# fbri_flight_straight.net
KiCad netlist of a schematic drawn in EAGLE
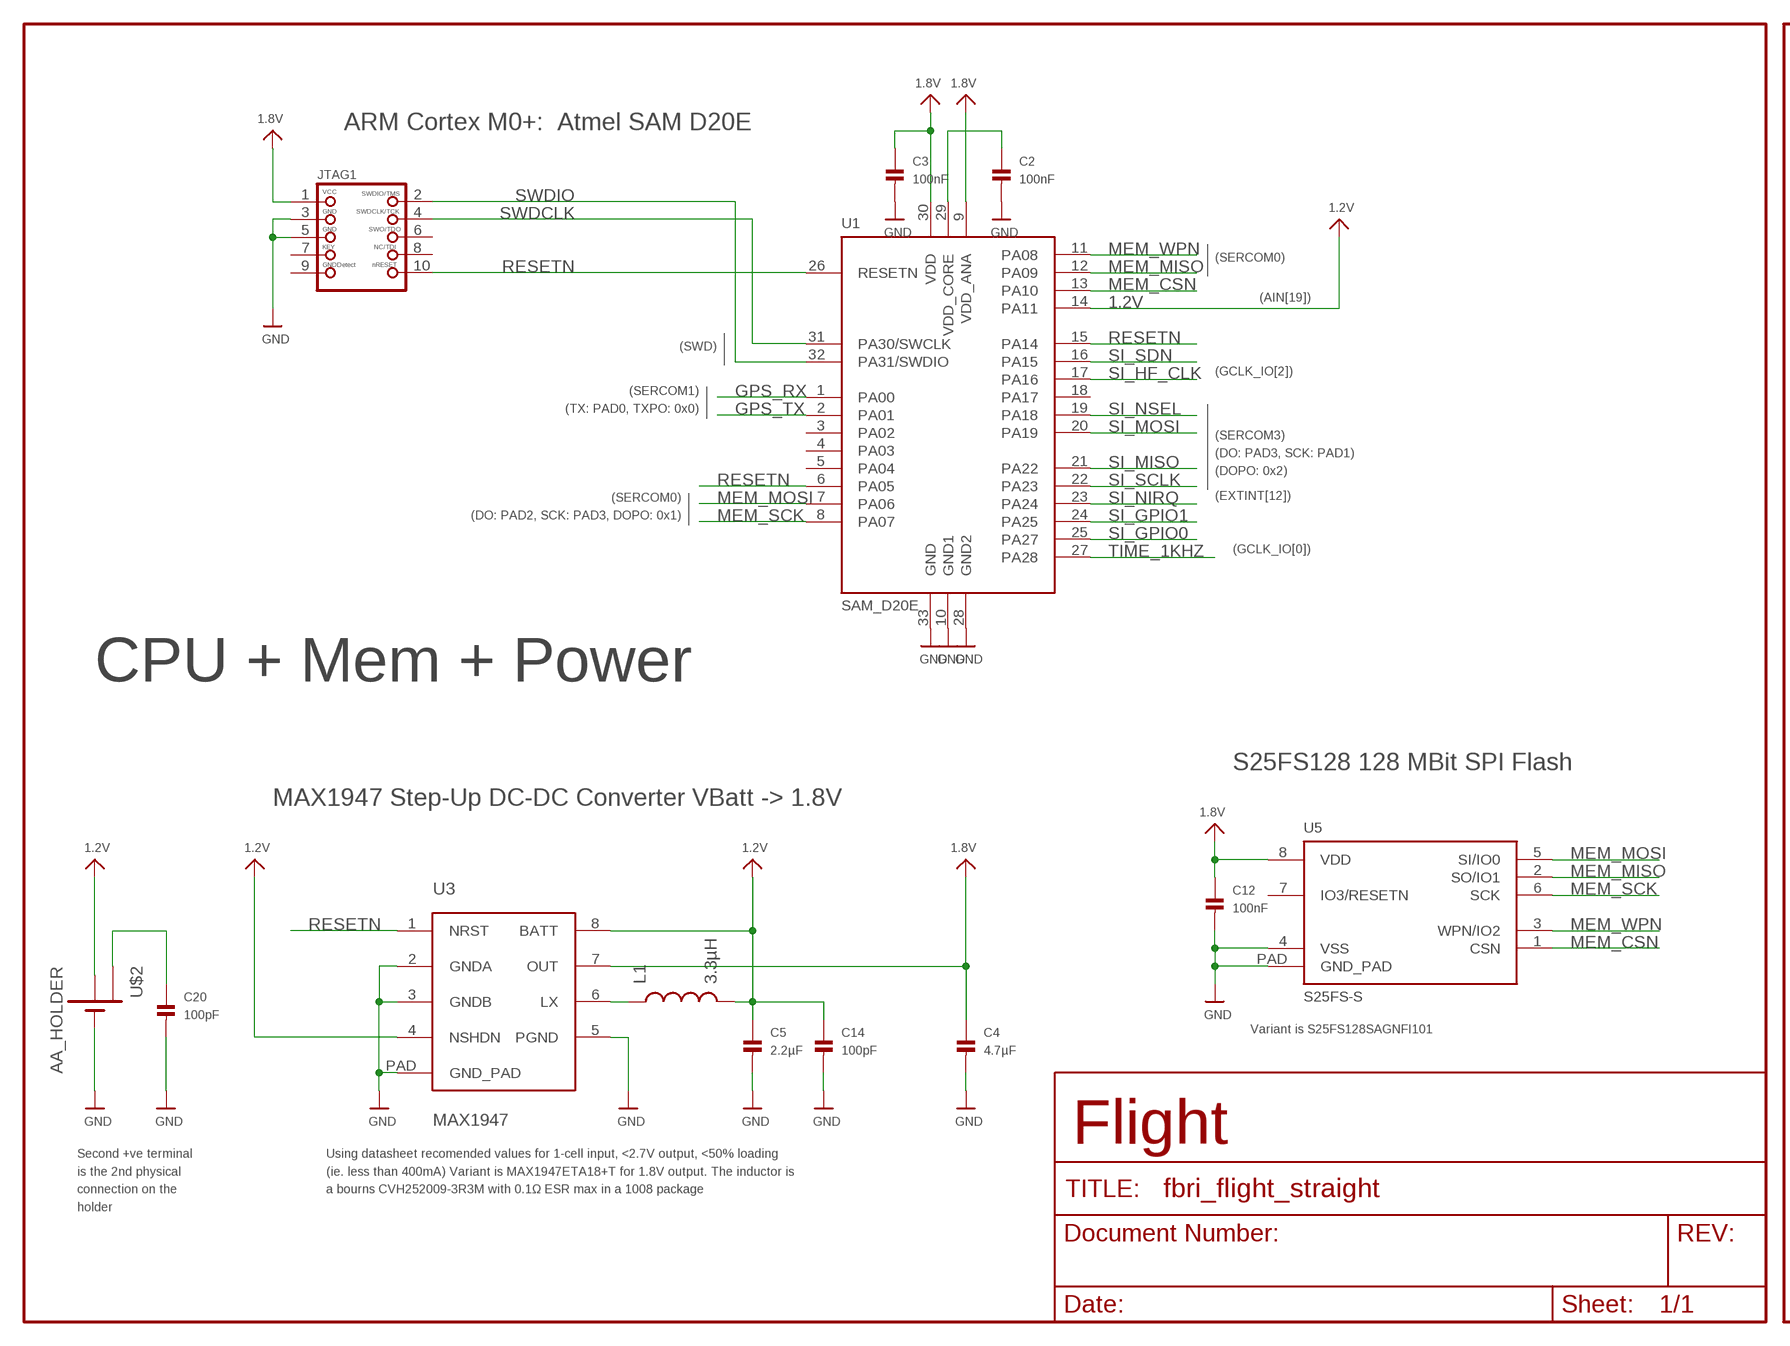
[diagram p0: schematic, sheet 1, part 1 of 2]
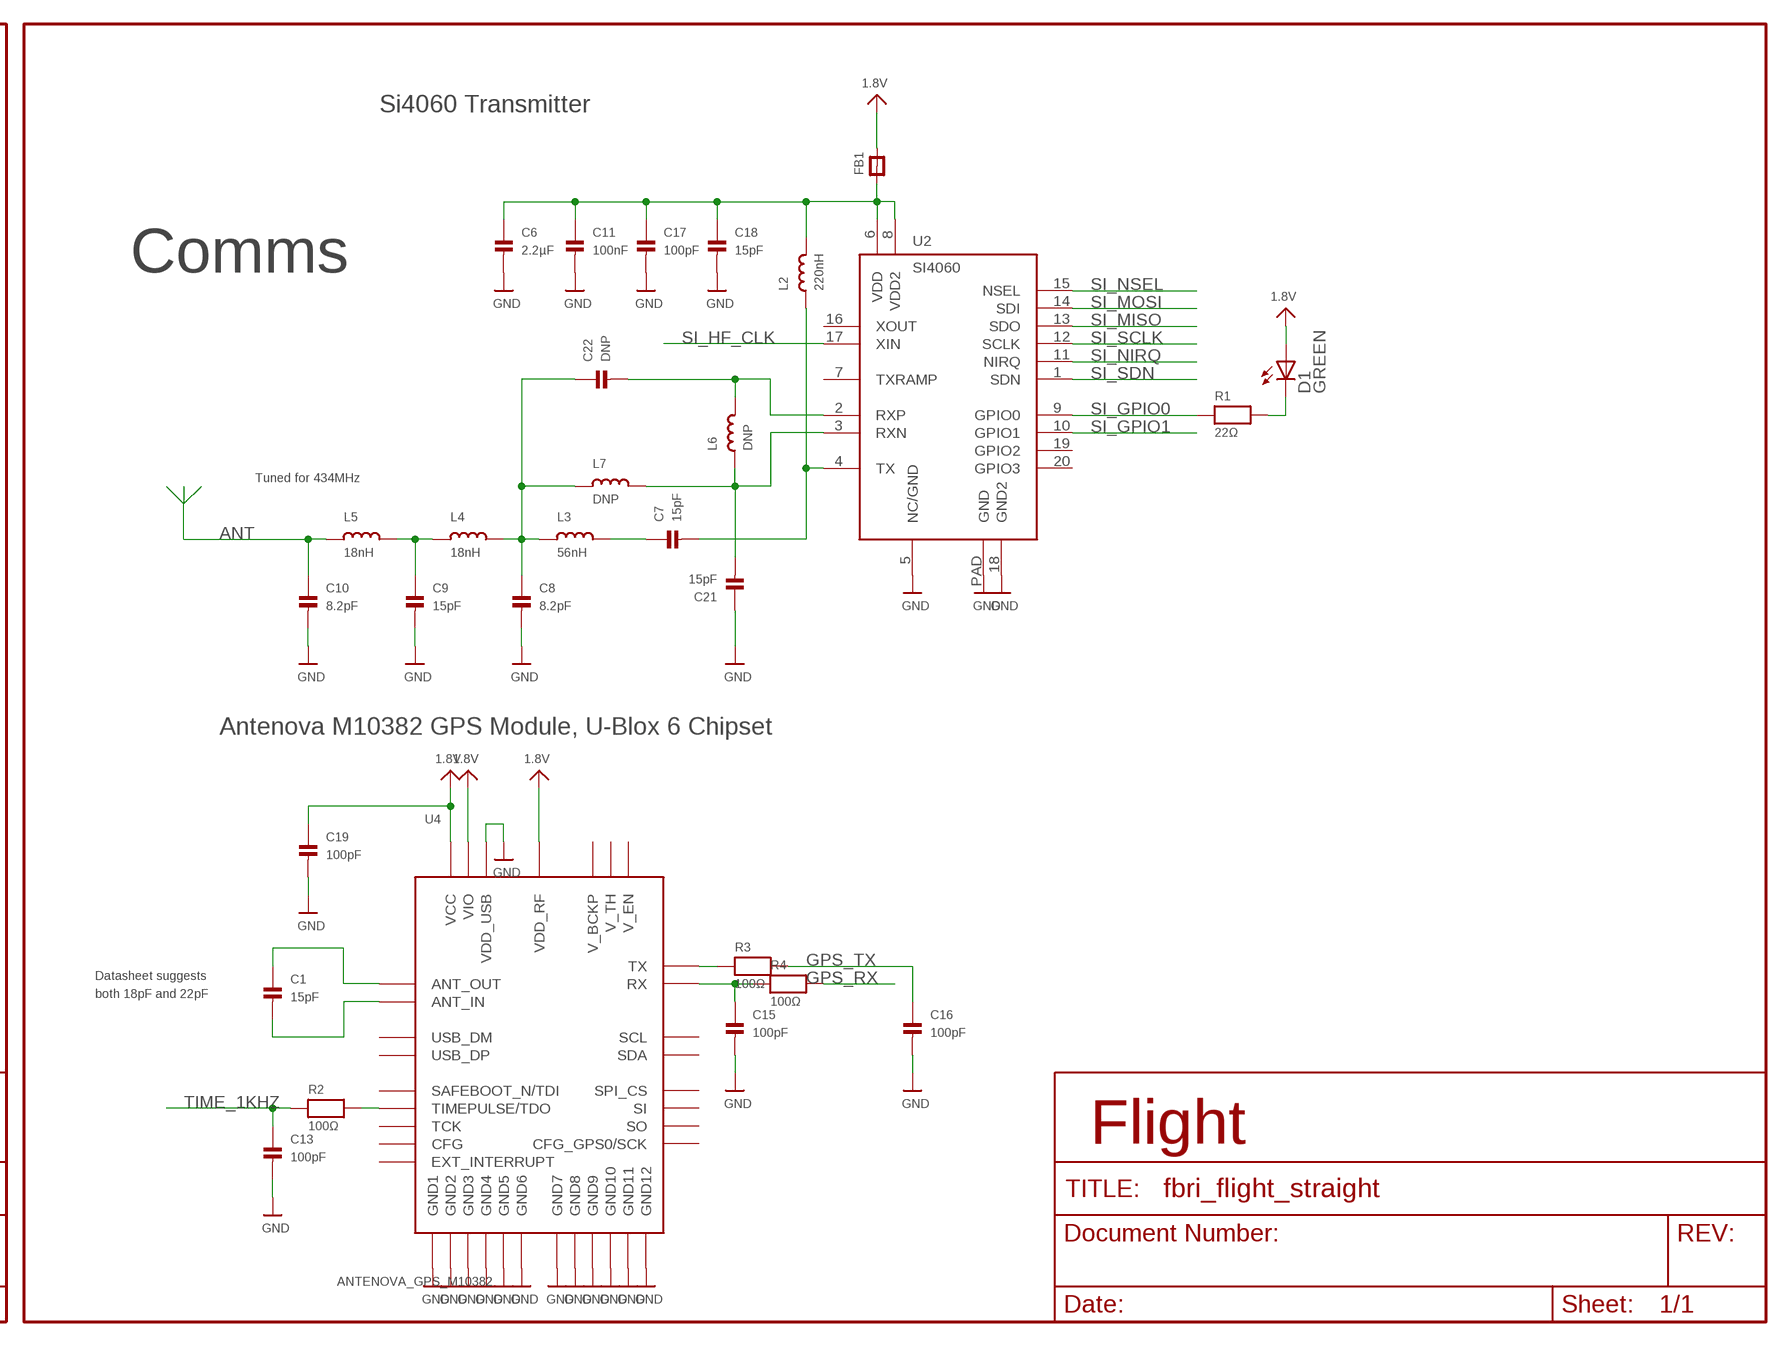
[diagram p1: schematic, sheet 1, part 2 of 2]

(export (version "E")
  (design (tool "Eeschema 10.0.6"))
  (components
    (comp (ref "C1")
      (value "15pF")
      (footprint "eagle-import:_0402")
      (libsource (lib "eagle-import") (part "CAP_CERAMIC_0402"))
    )
    (comp (ref "C2")
      (value "100nF")
      (footprint "eagle-import:_0402")
      (libsource (lib "eagle-import") (part "CAP_CERAMIC_0402"))
    )
    (comp (ref "C3")
      (value "100nF")
      (footprint "eagle-import:_0402")
      (libsource (lib "eagle-import") (part "CAP_CERAMIC_0402"))
    )
    (comp (ref "C4")
      (value "4.7µF")
      (footprint "eagle-import:_0402")
      (libsource (lib "eagle-import") (part "CAP_CERAMIC_0402"))
    )
    (comp (ref "C5")
      (value "2.2µF")
      (footprint "eagle-import:_0402")
      (libsource (lib "eagle-import") (part "CAP_CERAMIC_0402"))
    )
    (comp (ref "C6")
      (value "2.2µF")
      (footprint "eagle-import:_0402")
      (libsource (lib "eagle-import") (part "CAP_CERAMIC_0402"))
    )
    (comp (ref "C7")
      (value "15pF")
      (footprint "eagle-import:_0402")
      (libsource (lib "eagle-import") (part "CAP_CERAMIC_0402"))
    )
    (comp (ref "C8")
      (value "8.2pF")
      (footprint "eagle-import:_0402")
      (libsource (lib "eagle-import") (part "CAP_CERAMIC_0402"))
    )
    (comp (ref "C9")
      (value "15pF")
      (footprint "eagle-import:_0402")
      (libsource (lib "eagle-import") (part "CAP_CERAMIC_0402"))
    )
    (comp (ref "C10")
      (value "8.2pF")
      (footprint "eagle-import:_0402")
      (libsource (lib "eagle-import") (part "CAP_CERAMIC_0402"))
    )
    (comp (ref "C11")
      (value "100nF")
      (footprint "eagle-import:_0402")
      (libsource (lib "eagle-import") (part "CAP_CERAMIC_0402"))
    )
    (comp (ref "C12")
      (value "100nF")
      (footprint "eagle-import:_0402")
      (libsource (lib "eagle-import") (part "CAP_CERAMIC_0402"))
    )
    (comp (ref "C13")
      (value "100pF")
      (footprint "eagle-import:_0402")
      (libsource (lib "eagle-import") (part "CAP_CERAMIC_0402"))
    )
    (comp (ref "C14")
      (value "100pF")
      (footprint "eagle-import:_0402")
      (libsource (lib "eagle-import") (part "CAP_CERAMIC_0402"))
    )
    (comp (ref "C15")
      (value "100pF")
      (footprint "eagle-import:_0402")
      (libsource (lib "eagle-import") (part "CAP_CERAMIC_0402"))
    )
    (comp (ref "C16")
      (value "100pF")
      (footprint "eagle-import:_0402")
      (libsource (lib "eagle-import") (part "CAP_CERAMIC_0402"))
    )
    (comp (ref "C17")
      (value "100pF")
      (footprint "eagle-import:_0402")
      (libsource (lib "eagle-import") (part "CAP_CERAMIC_0402"))
    )
    (comp (ref "C18")
      (value "15pF")
      (footprint "eagle-import:_0402")
      (libsource (lib "eagle-import") (part "CAP_CERAMIC_0402"))
    )
    (comp (ref "C19")
      (value "100pF")
      (footprint "eagle-import:_0402")
      (libsource (lib "eagle-import") (part "CAP_CERAMIC_0402"))
    )
    (comp (ref "C20")
      (value "100pF")
      (footprint "eagle-import:_0402")
      (libsource (lib "eagle-import") (part "CAP_CERAMIC_0402"))
    )
    (comp (ref "C21")
      (value "15pF")
      (footprint "eagle-import:_0402")
      (libsource (lib "eagle-import") (part "CAP_CERAMIC_0402"))
    )
    (comp (ref "C22")
      (value "DNP")
      (footprint "eagle-import:_0402")
      (libsource (lib "eagle-import") (part "CAP_CERAMIC_0402"))
    )
    (comp (ref "D1")
      (value "GREEN")
      (footprint "eagle-import:CHIPLED_0603")
      (libsource (lib "eagle-import") (part "LEDCHIPLED_0603"))
    )
    (comp (ref "FB1")
      (value "FERRITE_0402")
      (footprint "eagle-import:_0402")
      (libsource (lib "eagle-import") (part "FERRITE_0402"))
    )
    (comp (ref "JTAG1")
      (value "JTAG-CORTEXM3SMT")
      (footprint "eagle-import:2X05_1.27MM_SMT")
      (libsource (lib "eagle-import") (part "JTAG-CORTEXM3SMT"))
    )
    (comp (ref "L1")
      (value "3.3µH")
      (footprint "eagle-import:1007")
      (libsource (lib "eagle-import") (part "INDUCTOR1007"))
    )
    (comp (ref "L2")
      (value "220nH")
      (footprint "eagle-import:_0402")
      (libsource (lib "eagle-import") (part "INDUCTOR_0402"))
    )
    (comp (ref "L3")
      (value "56nH")
      (footprint "eagle-import:_0402")
      (libsource (lib "eagle-import") (part "INDUCTOR_0402"))
    )
    (comp (ref "L4")
      (value "18nH")
      (footprint "eagle-import:_0402")
      (libsource (lib "eagle-import") (part "INDUCTOR_0402"))
    )
    (comp (ref "L5")
      (value "18nH")
      (footprint "eagle-import:_0402")
      (libsource (lib "eagle-import") (part "INDUCTOR_0402"))
    )
    (comp (ref "L6")
      (value "DNP")
      (footprint "eagle-import:_0402")
      (libsource (lib "eagle-import") (part "INDUCTOR_0402"))
    )
    (comp (ref "L7")
      (value "DNP")
      (footprint "eagle-import:_0402")
      (libsource (lib "eagle-import") (part "INDUCTOR_0402"))
    )
    (comp (ref "R1")
      (value "22Ω")
      (footprint "eagle-import:_0402")
      (libsource (lib "eagle-import") (part "RESISTOR_0402"))
    )
    (comp (ref "R2")
      (value "100Ω")
      (footprint "eagle-import:_0402")
      (libsource (lib "eagle-import") (part "RESISTOR_0402"))
    )
    (comp (ref "R3")
      (value "100Ω")
      (footprint "eagle-import:_0402")
      (libsource (lib "eagle-import") (part "RESISTOR_0402"))
    )
    (comp (ref "R4")
      (value "100Ω")
      (footprint "eagle-import:_0402")
      (libsource (lib "eagle-import") (part "RESISTOR_0402"))
    )
    (comp (ref "U$2")
      (value "AA_HOLDER")
      (footprint "eagle-import:AA")
      (libsource (lib "eagle-import") (part "AA_HOLDER"))
    )
    (comp (ref "U1")
      (value "SAM_D20E")
      (footprint "eagle-import:QFN32_5MM")
      (libsource (lib "eagle-import") (part "SAM_D20E"))
    )
    (comp (ref "U2")
      (value "SI4060")
      (footprint "eagle-import:QFN20")
      (libsource (lib "eagle-import") (part "SI4060"))
    )
    (comp (ref "U3")
      (value "MAX1947")
      (footprint "eagle-import:TDFN8")
      (libsource (lib "eagle-import") (part "MAX1947"))
    )
    (comp (ref "U4")
      (value "ANTENOVA_GPS_M10382")
      (footprint "eagle-import:ANTENOVA_GPS_M10382")
      (libsource (lib "eagle-import") (part "ANTENOVA_GPS_M10382"))
    )
    (comp (ref "U5")
      (value "S25FS-S")
      (footprint "eagle-import:WSON8")
      (libsource (lib "eagle-import") (part "S25FS-S"))
    )
  )
  (nets
    (net (code "1") (name "/ANT") (class "Default")
      (node (ref "C10") (pin "1") (pinfunction "P$1_1") (pintype "passive"))
      (node (ref "L5") (pin "1") (pinfunction "1_1") (pintype "passive"))
    )
    (net (code "2") (name "/GPS_RX") (class "Default")
      (node (ref "R4") (pin "2") (pinfunction "2_2") (pintype "passive"))
      (node (ref "U1") (pin "1") (pinfunction "PA00_1") (pintype "bidirectional"))
    )
    (net (code "3") (name "/GPS_TX") (class "Default")
      (node (ref "C16") (pin "1") (pinfunction "P$1_1") (pintype "passive"))
      (node (ref "R3") (pin "2") (pinfunction "2_2") (pintype "passive"))
      (node (ref "U1") (pin "2") (pinfunction "PA01_2") (pintype "bidirectional"))
    )
    (net (code "4") (name "/MEM_CSN") (class "Default")
      (node (ref "U1") (pin "13") (pinfunction "PA10_13") (pintype "bidirectional"))
      (node (ref "U5") (pin "1") (pinfunction "CSN_1") (pintype "input"))
    )
    (net (code "5") (name "/MEM_MISO") (class "Default")
      (node (ref "U1") (pin "12") (pinfunction "PA09_12") (pintype "bidirectional"))
      (node (ref "U5") (pin "2") (pinfunction "SO/IO1_2") (pintype "output"))
    )
    (net (code "6") (name "/MEM_MOSI") (class "Default")
      (node (ref "U1") (pin "7") (pinfunction "PA06_7") (pintype "bidirectional"))
      (node (ref "U5") (pin "5") (pinfunction "SI/IO0_5") (pintype "bidirectional"))
    )
    (net (code "7") (name "/MEM_SCK") (class "Default")
      (node (ref "U1") (pin "8") (pinfunction "PA07_8") (pintype "bidirectional"))
      (node (ref "U5") (pin "6") (pinfunction "SCK_6") (pintype "input"))
    )
    (net (code "8") (name "/MEM_WPN") (class "Default")
      (node (ref "U1") (pin "11") (pinfunction "PA08_11") (pintype "bidirectional"))
      (node (ref "U5") (pin "3") (pinfunction "WPN/IO2_3") (pintype "output"))
    )
    (net (code "9") (name "/RESETN") (class "Default")
      (node (ref "JTAG1") (pin "10") (pinfunction "10_10") (pintype "passive"))
      (node (ref "U1") (pin "15") (pinfunction "PA14_15") (pintype "bidirectional"))
      (node (ref "U1") (pin "26") (pinfunction "RESETN_26") (pintype "input"))
      (node (ref "U1") (pin "6") (pinfunction "PA05_6") (pintype "bidirectional"))
      (node (ref "U3") (pin "1") (pinfunction "NRST_1") (pintype "bidirectional"))
    )
    (net (code "10") (name "/SI_GPIO0") (class "Default")
      (node (ref "R1") (pin "1") (pinfunction "1_1") (pintype "passive"))
      (node (ref "U1") (pin "25") (pinfunction "PA27_25") (pintype "bidirectional"))
      (node (ref "U2") (pin "9") (pinfunction "GPIO0_9") (pintype "bidirectional"))
    )
    (net (code "11") (name "/SI_GPIO1") (class "Default")
      (node (ref "U1") (pin "24") (pinfunction "PA25_24") (pintype "bidirectional"))
      (node (ref "U2") (pin "10") (pinfunction "GPIO1_10") (pintype "bidirectional"))
    )
    (net (code "12") (name "/SI_HF_CLK") (class "Default")
      (node (ref "U1") (pin "17") (pinfunction "PA16_17") (pintype "bidirectional"))
      (node (ref "U2") (pin "17") (pinfunction "XIN_17") (pintype "input"))
    )
    (net (code "13") (name "/SI_MISO") (class "Default")
      (node (ref "U1") (pin "21") (pinfunction "PA22_21") (pintype "bidirectional"))
      (node (ref "U2") (pin "13") (pinfunction "SDO_13") (pintype "output"))
    )
    (net (code "14") (name "/SI_MOSI") (class "Default")
      (node (ref "U1") (pin "20") (pinfunction "PA19_20") (pintype "bidirectional"))
      (node (ref "U2") (pin "14") (pinfunction "SDI_14") (pintype "bidirectional"))
    )
    (net (code "15") (name "/SI_NIRQ") (class "Default")
      (node (ref "U1") (pin "23") (pinfunction "PA24_23") (pintype "bidirectional"))
      (node (ref "U2") (pin "11") (pinfunction "NIRQ_11") (pintype "output"))
    )
    (net (code "16") (name "/SI_NSEL") (class "Default")
      (node (ref "U1") (pin "19") (pinfunction "PA18_19") (pintype "bidirectional"))
      (node (ref "U2") (pin "15") (pinfunction "NSEL_15") (pintype "input"))
    )
    (net (code "17") (name "/SI_SCLK") (class "Default")
      (node (ref "U1") (pin "22") (pinfunction "PA23_22") (pintype "bidirectional"))
      (node (ref "U2") (pin "12") (pinfunction "SCLK_12") (pintype "input"))
    )
    (net (code "18") (name "/SI_SDN") (class "Default")
      (node (ref "U1") (pin "16") (pinfunction "PA15_16") (pintype "bidirectional"))
      (node (ref "U2") (pin "1") (pinfunction "SDN_1") (pintype "input"))
    )
    (net (code "19") (name "/SWDCLK") (class "Default")
      (node (ref "JTAG1") (pin "4") (pinfunction "4_4") (pintype "passive"))
      (node (ref "U1") (pin "31") (pinfunction "PA30/SWCLK_31") (pintype "bidirectional"))
    )
    (net (code "20") (name "/SWDIO") (class "Default")
      (node (ref "JTAG1") (pin "2") (pinfunction "2_2") (pintype "passive"))
      (node (ref "U1") (pin "32") (pinfunction "PA31/SWDIO_32") (pintype "bidirectional"))
    )
    (net (code "21") (name "/TIME_1KHZ") (class "Default")
      (node (ref "C13") (pin "1") (pinfunction "P$1_1") (pintype "passive"))
      (node (ref "R2") (pin "1") (pinfunction "1_1") (pintype "passive"))
      (node (ref "U1") (pin "27") (pinfunction "PA28_27") (pintype "bidirectional"))
    )
    (net (code "22") (name "1.2V") (class "Default")
      (node (ref "C14") (pin "1") (pinfunction "P$1_1") (pintype "passive"))
      (node (ref "C5") (pin "1") (pinfunction "P$1_1") (pintype "passive"))
      (node (ref "L1") (pin "2") (pinfunction "2_2") (pintype "passive"))
      (node (ref "U$2") (pin "+2") (pinfunction "+_+2") (pintype "power_in"))
      (node (ref "U1") (pin "14") (pinfunction "PA11_14") (pintype "bidirectional"))
      (node (ref "U3") (pin "4") (pinfunction "NSHDN_4") (pintype "bidirectional"))
      (node (ref "U3") (pin "8") (pinfunction "BATT_8") (pintype "bidirectional"))
    )
    (net (code "23") (name "1.8V") (class "Default")
      (node (ref "C12") (pin "1") (pinfunction "P$1_1") (pintype "passive"))
      (node (ref "C19") (pin "1") (pinfunction "P$1_1") (pintype "passive"))
      (node (ref "C3") (pin "1") (pinfunction "P$1_1") (pintype "passive"))
      (node (ref "C4") (pin "1") (pinfunction "P$1_1") (pintype "passive"))
      (node (ref "D1") (pin "A") (pinfunction "A_A") (pintype "passive"))
      (node (ref "FB1") (pin "2") (pinfunction "P$2_2") (pintype "passive"))
      (node (ref "JTAG1") (pin "1") (pinfunction "1_1") (pintype "passive"))
      (node (ref "U1") (pin "30") (pinfunction "VDD_30") (pintype "power_in"))
      (node (ref "U1") (pin "9") (pinfunction "VDD_ANA_9") (pintype "power_in"))
      (node (ref "U3") (pin "7") (pinfunction "OUT_7") (pintype "bidirectional"))
      (node (ref "U4") (pin "25_VDD_RF") (pinfunction "VDD_RF_25_VDD_RF") (pintype "power_in"))
      (node (ref "U4") (pin "27_VCC") (pinfunction "VCC_27_VCC") (pintype "power_in"))
      (node (ref "U4") (pin "5_VIO") (pinfunction "VIO_5_VIO") (pintype "bidirectional"))
      (node (ref "U5") (pin "8") (pinfunction "VDD_8") (pintype "power_in"))
    )
    (net (code "24") (name "GND") (class "Default")
      (node (ref "C10") (pin "2") (pinfunction "P$2_2") (pintype "passive"))
      (node (ref "C11") (pin "2") (pinfunction "P$2_2") (pintype "passive"))
      (node (ref "C12") (pin "2") (pinfunction "P$2_2") (pintype "passive"))
      (node (ref "C13") (pin "2") (pinfunction "P$2_2") (pintype "passive"))
      (node (ref "C14") (pin "2") (pinfunction "P$2_2") (pintype "passive"))
      (node (ref "C15") (pin "2") (pinfunction "P$2_2") (pintype "passive"))
      (node (ref "C16") (pin "2") (pinfunction "P$2_2") (pintype "passive"))
      (node (ref "C17") (pin "2") (pinfunction "P$2_2") (pintype "passive"))
      (node (ref "C18") (pin "2") (pinfunction "P$2_2") (pintype "passive"))
      (node (ref "C19") (pin "2") (pinfunction "P$2_2") (pintype "passive"))
      (node (ref "C2") (pin "2") (pinfunction "P$2_2") (pintype "passive"))
      (node (ref "C20") (pin "2") (pinfunction "P$2_2") (pintype "passive"))
      (node (ref "C21") (pin "1") (pinfunction "P$1_1") (pintype "passive"))
      (node (ref "C3") (pin "2") (pinfunction "P$2_2") (pintype "passive"))
      (node (ref "C4") (pin "2") (pinfunction "P$2_2") (pintype "passive"))
      (node (ref "C5") (pin "2") (pinfunction "P$2_2") (pintype "passive"))
      (node (ref "C6") (pin "2") (pinfunction "P$2_2") (pintype "passive"))
      (node (ref "C8") (pin "2") (pinfunction "P$2_2") (pintype "passive"))
      (node (ref "C9") (pin "2") (pinfunction "P$2_2") (pintype "passive"))
      (node (ref "JTAG1") (pin "3") (pinfunction "3_3") (pintype "passive"))
      (node (ref "JTAG1") (pin "5") (pinfunction "5_5") (pintype "passive"))
      (node (ref "U$2") (pin "-1") (pinfunction "-_-1") (pintype "power_in"))
      (node (ref "U$2") (pin "-2") (pinfunction "-_-2") (pintype "power_in"))
      (node (ref "U1") (pin "10") (pinfunction "GND1_10") (pintype "power_in"))
      (node (ref "U1") (pin "28") (pinfunction "GND2_28") (pintype "power_in"))
      (node (ref "U1") (pin "33") (pinfunction "GND_33") (pintype "power_in"))
      (node (ref "U2") (pin "18") (pinfunction "GND2_18") (pintype "power_in"))
      (node (ref "U2") (pin "5") (pinfunction "NC/GND_5") (pintype "bidirectional"))
      (node (ref "U2") (pin "PAD") (pinfunction "GND_PAD") (pintype "power_in"))
      (node (ref "U3") (pin "2") (pinfunction "GNDA_2") (pintype "bidirectional"))
      (node (ref "U3") (pin "3") (pinfunction "GNDB_3") (pintype "bidirectional"))
      (node (ref "U3") (pin "5") (pinfunction "PGND_5") (pintype "bidirectional"))
      (node (ref "U3") (pin "PAD") (pinfunction "GND_PAD_PAD") (pintype "bidirectional"))
      (node (ref "U4") (pin "14_GND") (pinfunction "GND3_14_GND") (pintype "power_in"))
      (node (ref "U4") (pin "17_GND") (pinfunction "GND4_17_GND") (pintype "power_in"))
      (node (ref "U4") (pin "21_GND") (pinfunction "GND5_21_GND") (pintype "bidirectional"))
      (node (ref "U4") (pin "24_GND") (pinfunction "GND6_24_GND") (pintype "bidirectional"))
      (node (ref "U4") (pin "26_GND") (pinfunction "GND7_26_GND") (pintype "power_in"))
      (node (ref "U4") (pin "28_GND") (pinfunction "GND8_28_GND") (pintype "power_in"))
      (node (ref "U4") (pin "2_GND") (pinfunction "GND1_2_GND") (pintype "power_in"))
      (node (ref "U4") (pin "32_VDD_USB") (pinfunction "VDD_USB_32_VDD_USB") (pintype "bidirectional"))
      (node (ref "U4") (pin "33_GND") (pinfunction "GND9_33_GND") (pintype "power_in"))
      (node (ref "U4") (pin "34_GND") (pinfunction "GND10_34_GND") (pintype "power_in"))
      (node (ref "U4") (pin "35_GND") (pinfunction "GND11_35_GND") (pintype "bidirectional"))
      (node (ref "U4") (pin "36_GND") (pinfunction "GND12_36_GND") (pintype "bidirectional"))
      (node (ref "U4") (pin "4_GND") (pinfunction "GND2_4_GND") (pintype "power_in"))
      (node (ref "U5") (pin "4") (pinfunction "VSS_4") (pintype "power_in"))
      (node (ref "U5") (pin "PAD") (pinfunction "GND_PAD_PAD") (pintype "power_in"))
    )
    (net (code "25") (name "Net-(C1-P$1)") (class "Default")
      (node (ref "C1") (pin "1") (pinfunction "P$1_1") (pintype "passive"))
      (node (ref "U4") (pin "3_ANT_OUT") (pinfunction "ANT_OUT_3_ANT_OUT") (pintype "output"))
    )
    (net (code "26") (name "Net-(C1-P$2)") (class "Default")
      (node (ref "C1") (pin "2") (pinfunction "P$2_2") (pintype "passive"))
      (node (ref "U4") (pin "1_ANT_IN") (pinfunction "ANT_IN_1_ANT_IN") (pintype "input"))
    )
    (net (code "27") (name "Net-(C2-P$1)") (class "Default")
      (node (ref "C2") (pin "1") (pinfunction "P$1_1") (pintype "passive"))
      (node (ref "U1") (pin "29") (pinfunction "VDD_CORE_29") (pintype "power_in"))
    )
    (net (code "28") (name "Net-(C7-P$1)") (class "Default")
      (node (ref "C7") (pin "1") (pinfunction "P$1_1") (pintype "passive"))
      (node (ref "L3") (pin "2") (pinfunction "2_2") (pintype "passive"))
    )
    (net (code "29") (name "Net-(C7-P$2)") (class "Default")
      (node (ref "C7") (pin "2") (pinfunction "P$2_2") (pintype "passive"))
      (node (ref "L2") (pin "1") (pinfunction "1_1") (pintype "passive"))
      (node (ref "U2") (pin "4") (pinfunction "TX_4") (pintype "output"))
    )
    (net (code "30") (name "Net-(C9-P$1)") (class "Default")
      (node (ref "C9") (pin "1") (pinfunction "P$1_1") (pintype "passive"))
      (node (ref "L4") (pin "1") (pinfunction "1_1") (pintype "passive"))
      (node (ref "L5") (pin "2") (pinfunction "2_2") (pintype "passive"))
    )
    (net (code "31") (name "Net-(C11-P$1)") (class "Default")
      (node (ref "C11") (pin "1") (pinfunction "P$1_1") (pintype "passive"))
      (node (ref "C17") (pin "1") (pinfunction "P$1_1") (pintype "passive"))
      (node (ref "C18") (pin "1") (pinfunction "P$1_1") (pintype "passive"))
      (node (ref "C6") (pin "1") (pinfunction "P$1_1") (pintype "passive"))
      (node (ref "FB1") (pin "1") (pinfunction "P$1_1") (pintype "passive"))
      (node (ref "L2") (pin "2") (pinfunction "2_2") (pintype "passive"))
      (node (ref "U2") (pin "6") (pinfunction "VDD_6") (pintype "power_in"))
      (node (ref "U2") (pin "8") (pinfunction "VDD2_8") (pintype "power_in"))
    )
    (net (code "32") (name "Net-(C15-P$1)") (class "Default")
      (node (ref "C15") (pin "1") (pinfunction "P$1_1") (pintype "passive"))
      (node (ref "R4") (pin "1") (pinfunction "1_1") (pintype "passive"))
      (node (ref "U4") (pin "13_RX") (pinfunction "RX_13_RX") (pintype "bidirectional"))
    )
    (net (code "33") (name "Net-(C20-P$1)") (class "Default")
      (node (ref "C20") (pin "1") (pinfunction "P$1_1") (pintype "passive"))
      (node (ref "U$2") (pin "+1") (pinfunction "+2_+1") (pintype "power_in"))
    )
    (net (code "34") (name "Net-(C21-P$2)") (class "Default")
      (node (ref "C21") (pin "2") (pinfunction "P$2_2") (pintype "passive"))
      (node (ref "L6") (pin "1") (pinfunction "1_1") (pintype "passive"))
      (node (ref "L7") (pin "2") (pinfunction "2_2") (pintype "passive"))
      (node (ref "U2") (pin "3") (pinfunction "RXN_3") (pintype "input"))
    )
    (net (code "35") (name "Net-(C22-P$1)") (class "Default")
      (node (ref "C22") (pin "1") (pinfunction "P$1_1") (pintype "passive"))
      (node (ref "C8") (pin "1") (pinfunction "P$1_1") (pintype "passive"))
      (node (ref "L3") (pin "1") (pinfunction "1_1") (pintype "passive"))
      (node (ref "L4") (pin "2") (pinfunction "2_2") (pintype "passive"))
      (node (ref "L7") (pin "1") (pinfunction "1_1") (pintype "passive"))
    )
    (net (code "36") (name "Net-(C22-P$2)") (class "Default")
      (node (ref "C22") (pin "2") (pinfunction "P$2_2") (pintype "passive"))
      (node (ref "L6") (pin "2") (pinfunction "2_2") (pintype "passive"))
      (node (ref "U2") (pin "2") (pinfunction "RXP_2") (pintype "input"))
    )
    (net (code "37") (name "Net-(D1-PadC)") (class "Default")
      (node (ref "D1") (pin "C") (pinfunction "C_C") (pintype "passive"))
      (node (ref "R1") (pin "2") (pinfunction "2_2") (pintype "passive"))
    )
    (net (code "38") (name "Net-(U3-LX)") (class "Default")
      (node (ref "L1") (pin "1") (pinfunction "1_1") (pintype "passive"))
      (node (ref "U3") (pin "6") (pinfunction "LX_6") (pintype "bidirectional"))
    )
    (net (code "39") (name "Net-(U4-TIMEPULSE{slash}TDO)") (class "Default")
      (node (ref "R2") (pin "2") (pinfunction "2_2") (pintype "passive"))
      (node (ref "U4") (pin "23_TIMEPULSE/TDO") (pinfunction "TIMEPULSE/TDO_23_TIMEPULSE/TDO") (pintype "bidirectional"))
    )
    (net (code "40") (name "Net-(U4-TX)") (class "Default")
      (node (ref "R3") (pin "1") (pinfunction "1_1") (pintype "passive"))
      (node (ref "U4") (pin "11_TX") (pinfunction "TX_11_TX") (pintype "bidirectional"))
    )
    (net (code "41") (name "unconnected-(JTAG1-Pad6)") (class "Default")
      (node (ref "JTAG1") (pin "6") (pinfunction "6_6") (pintype "passive"))
    )
    (net (code "42") (name "unconnected-(JTAG1-Pad7)") (class "Default")
      (node (ref "JTAG1") (pin "7") (pinfunction "7_7") (pintype "passive"))
    )
    (net (code "43") (name "unconnected-(JTAG1-Pad8)") (class "Default")
      (node (ref "JTAG1") (pin "8") (pinfunction "8_8") (pintype "passive"))
    )
    (net (code "44") (name "unconnected-(JTAG1-Pad9)") (class "Default")
      (node (ref "JTAG1") (pin "9") (pinfunction "9_9") (pintype "passive"))
    )
    (net (code "45") (name "unconnected-(U1-PA02-Pad3)") (class "Default")
      (node (ref "U1") (pin "3") (pinfunction "PA02_3") (pintype "bidirectional"))
    )
    (net (code "46") (name "unconnected-(U1-PA03-Pad4)") (class "Default")
      (node (ref "U1") (pin "4") (pinfunction "PA03_4") (pintype "bidirectional"))
    )
    (net (code "47") (name "unconnected-(U1-PA04-Pad5)") (class "Default")
      (node (ref "U1") (pin "5") (pinfunction "PA04_5") (pintype "bidirectional"))
    )
    (net (code "48") (name "unconnected-(U1-PA17-Pad18)") (class "Default")
      (node (ref "U1") (pin "18") (pinfunction "PA17_18") (pintype "bidirectional"))
    )
    (net (code "49") (name "unconnected-(U2-GPIO2-Pad19)") (class "Default")
      (node (ref "U2") (pin "19") (pinfunction "GPIO2_19") (pintype "bidirectional"))
    )
    (net (code "50") (name "unconnected-(U2-GPIO3-Pad20)") (class "Default")
      (node (ref "U2") (pin "20") (pinfunction "GPIO3_20") (pintype "bidirectional"))
    )
    (net (code "51") (name "unconnected-(U2-TXRAMP-Pad7)") (class "Default")
      (node (ref "U2") (pin "7") (pinfunction "TXRAMP_7") (pintype "bidirectional"))
    )
    (net (code "52") (name "unconnected-(U2-XOUT-Pad16)") (class "Default")
      (node (ref "U2") (pin "16") (pinfunction "XOUT_16") (pintype "output"))
    )
    (net (code "53") (name "unconnected-(U4-CFG-Pad31_CFG)") (class "Default")
      (node (ref "U4") (pin "31_CFG") (pinfunction "CFG_31_CFG") (pintype "bidirectional"))
    )
    (net (code "54") (name "unconnected-(U4-CFG_GPS0{slash}SCK-Pad9_CFG_GPS0_SCK)") (class "Default")
      (node (ref "U4") (pin "9_CFG_GPS0_SCK") (pinfunction "CFG_GPS0/SCK_9_CFG_GPS0_SCK") (pintype "bidirectional"))
    )
    (net (code "55") (name "unconnected-(U4-EXT_INTERRUPT-Pad29_EXT_INTERRUPT)") (class "Default")
      (node (ref "U4") (pin "29_EXT_INTERRUPT") (pinfunction "EXT_INTERRUPT_29_EXT_INTERRUPT") (pintype "bidirectional"))
    )
    (net (code "56") (name "unconnected-(U4-SAFEBOOT_N{slash}TDI-Pad20_SAFEBOOT_N{slash}TDI)") (class "Default")
      (node (ref "U4") (pin "20_SAFEBOOT_N/TDI") (pinfunction "SAFEBOOT_N/TDI_20_SAFEBOOT_N/TDI") (pintype "bidirectional"))
    )
    (net (code "57") (name "unconnected-(U4-SCL-Pad19_SCL)") (class "Default")
      (node (ref "U4") (pin "19_SCL") (pinfunction "SCL_19_SCL") (pintype "bidirectional"))
    )
    (net (code "58") (name "unconnected-(U4-SDA-Pad18_SDA)") (class "Default")
      (node (ref "U4") (pin "18_SDA") (pinfunction "SDA_18_SDA") (pintype "bidirectional"))
    )
    (net (code "59") (name "unconnected-(U4-SI-Pad16_SI)") (class "Default")
      (node (ref "U4") (pin "16_SI") (pinfunction "SI_16_SI") (pintype "bidirectional"))
    )
    (net (code "60") (name "unconnected-(U4-SO-Pad8_SO)") (class "Default")
      (node (ref "U4") (pin "8_SO") (pinfunction "SO_8_SO") (pintype "bidirectional"))
    )
    (net (code "61") (name "unconnected-(U4-SPI_CS-Pad10_SPI_SELECT)") (class "Default")
      (node (ref "U4") (pin "10_SPI_SELECT") (pinfunction "SPI_CS_10_SPI_SELECT") (pintype "bidirectional"))
    )
    (net (code "62") (name "unconnected-(U4-TCK-Pad22_TCK)") (class "Default")
      (node (ref "U4") (pin "22_TCK") (pinfunction "TCK_22_TCK") (pintype "bidirectional"))
    )
    (net (code "63") (name "unconnected-(U4-USB_DM-Pad7_USB_DM)") (class "Default")
      (node (ref "U4") (pin "7_USB_DM") (pinfunction "USB_DM_7_USB_DM") (pintype "bidirectional"))
    )
    (net (code "64") (name "unconnected-(U4-USB_DP-Pad6_USB_DP)") (class "Default")
      (node (ref "U4") (pin "6_USB_DP") (pinfunction "USB_DP_6_USB_DP") (pintype "bidirectional"))
    )
    (net (code "65") (name "unconnected-(U4-V_BCKP-Pad15_V_BCKUP)") (class "Default")
      (node (ref "U4") (pin "15_V_BCKUP") (pinfunction "V_BCKP_15_V_BCKUP") (pintype "bidirectional"))
    )
    (net (code "66") (name "unconnected-(U4-V_EN-Pad30_V_EN)") (class "Default")
      (node (ref "U4") (pin "30_V_EN") (pinfunction "V_EN_30_V_EN") (pintype "bidirectional"))
    )
    (net (code "67") (name "unconnected-(U4-V_TH-Pad12_V_TH)") (class "Default")
      (node (ref "U4") (pin "12_V_TH") (pinfunction "V_TH_12_V_TH") (pintype "bidirectional"))
    )
    (net (code "68") (name "unconnected-(U5-IO3{slash}RESETN-Pad7)") (class "Default")
      (node (ref "U5") (pin "7") (pinfunction "IO3/RESETN_7") (pintype "output"))
    )
  )
)
